# usb.net
KiCad netlist of a schematic drawn in Altium Designer
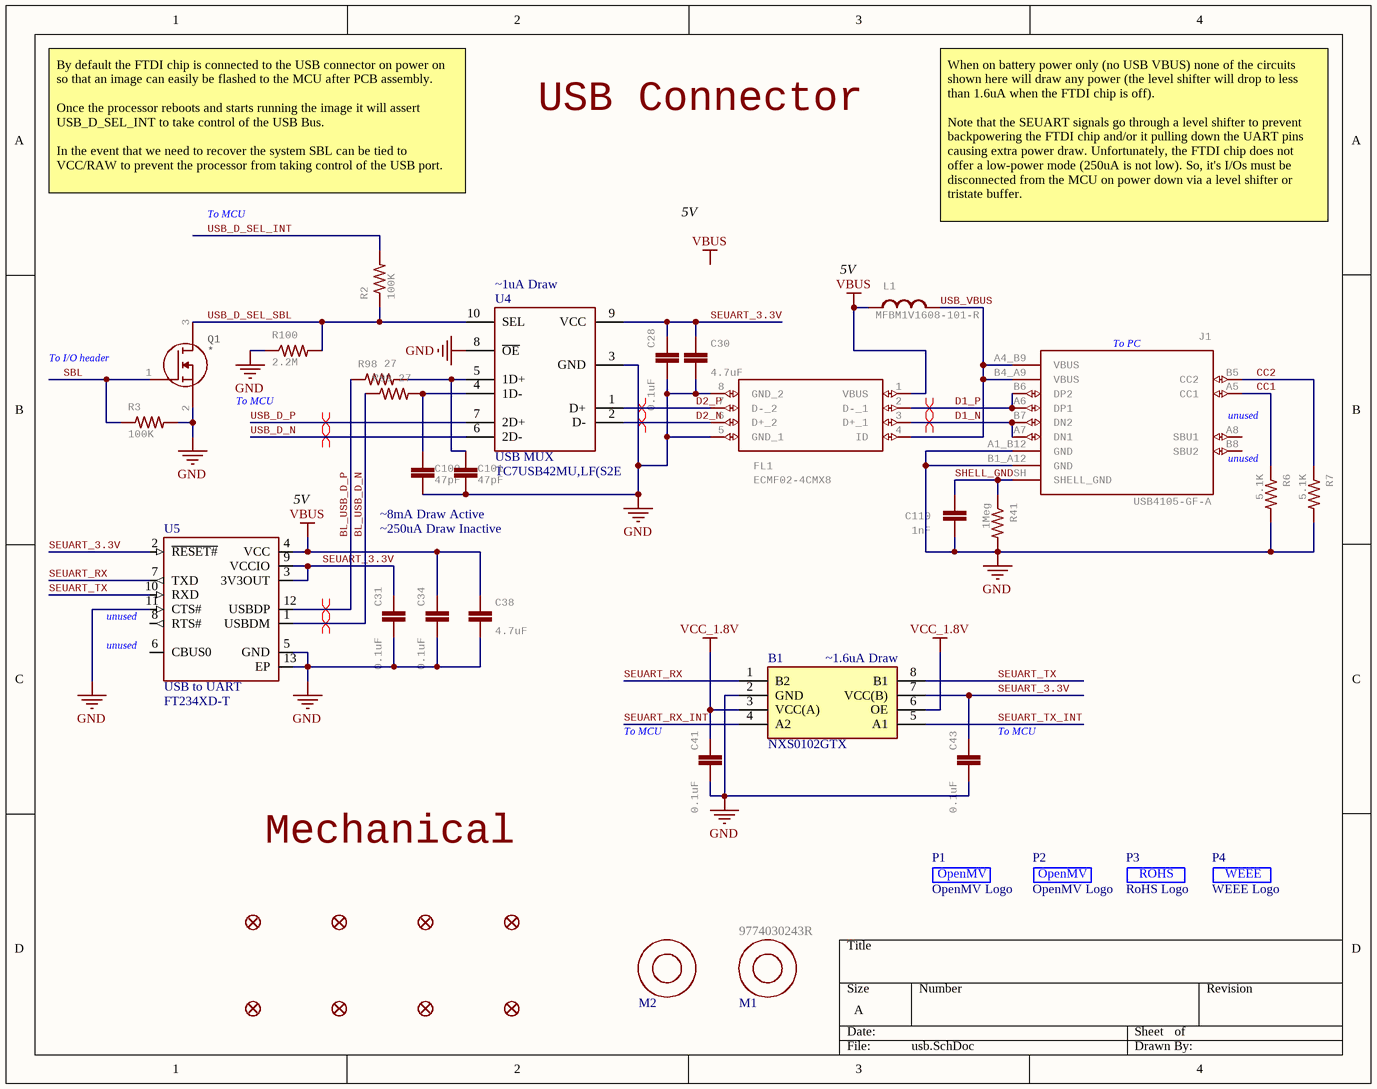
[diagram p0: usb.SchDoc]

(export (version "E")
  (design (tool "Eeschema 10.0.6"))
  (components
    (comp (ref "B1")
      (value "NXS0102GTX")
      (footprint "NXS0102GTX")
      (description "Dual supply translating transceiver; open drain; auto direction sensing")
      (fields (field (name "MOUSER PART NUMBER") "771-NXS0102GTX"))
      (libsource (lib "openmv-ae3") (part "NXS0102GTX"))
    )
    (comp (ref "C28")
      (value "0.1uF")
      (footprint "0402-CAP")
      (description "CAPACITOR, European symbol")
      (fields (field (name "MPN") "C0402C104Z4VAC"))
      (libsource (lib "openmv-ae3") (part "C-EUC0201"))
    )
    (comp (ref "C30")
      (value "4.7uF")
      (footprint "0402-CAP")
      (description "CapacitorStandard 0603 ceramic capacitor, and 0.1\" leaded capacitor.")
      (fields (field (name "MPN") "JMK105BBJ475MV-F") (field (name "LIBRARYNAME") "sfe"))
      (libsource (lib "") (part "CAP0402-CAP_1"))
    )
    (comp (ref "C31")
      (value "0.1uF")
      (footprint "0402-CAP")
      (description "CAPACITOR, European symbol")
      (fields (field (name "MPN") "C0402C104Z4VAC"))
      (libsource (lib "openmv-ae3") (part "C-EUC0201"))
    )
    (comp (ref "C34")
      (value "0.1uF")
      (footprint "0402-CAP")
      (description "CAPACITOR, European symbol")
      (fields (field (name "MPN") "C0402C104Z4VAC"))
      (libsource (lib "openmv-ae3") (part "C-EUC0201"))
    )
    (comp (ref "C38")
      (value "4.7uF")
      (footprint "0402-CAP")
      (description "CapacitorStandard 0603 ceramic capacitor, and 0.1\" leaded capacitor.")
      (fields (field (name "MPN") "JMK105BBJ475MV-F") (field (name "LIBRARYNAME") "sfe"))
      (libsource (lib "") (part "CAP0402-CAP_1"))
    )
    (comp (ref "C41")
      (value "0.1uF")
      (footprint "0402-CAP")
      (description "CAPACITOR, European symbol")
      (fields (field (name "MPN") "C0402C104Z4VAC"))
      (libsource (lib "openmv-ae3") (part "C-EUC0201"))
    )
    (comp (ref "C43")
      (value "0.1uF")
      (footprint "0402-CAP")
      (description "CAPACITOR, European symbol")
      (fields (field (name "MPN") "C0402C104Z4VAC"))
      (libsource (lib "openmv-ae3") (part "C-EUC0201"))
    )
    (comp (ref "C100")
      (value "47pF")
      (footprint "C0201")
      (description "CAPACITOR, European symbol")
      (libsource (lib "") (part "C-EUC0201_1"))
    )
    (comp (ref "C101")
      (value "47pF")
      (footprint "C0201")
      (description "CAPACITOR, European symbol")
      (libsource (lib "") (part "C-EUC0201_1"))
    )
    (comp (ref "C110")
      (value "1nF")
      (footprint "0402-CAP")
      (description "Capacitor")
      (fields (field (name "MPN") "VJ0402Y102JXACW1BC") (field (name "LIBRARYNAME") "sfe"))
      (libsource (lib "openmv-ae3") (part "CAP0402-CAP"))
    )
    (comp (ref "FD1")
      (value "FIDUCIAL1X2")
      (footprint "FIDUCIAL-1X2")
      (fields (field (name "LIBRARYNAME") "SparkFun-Aesthetics"))
      (libsource (lib "openmv-ae3") (part "FIDUCIAL1X2"))
    )
    (comp (ref "FD2")
      (value "FIDUCIAL1X2")
      (footprint "FIDUCIAL-1X2")
      (fields (field (name "LIBRARYNAME") "SparkFun-Aesthetics"))
      (libsource (lib "openmv-ae3") (part "FIDUCIAL1X2"))
    )
    (comp (ref "FD3")
      (value "FIDUCIAL1X2")
      (footprint "FIDUCIAL-1X2")
      (fields (field (name "LIBRARYNAME") "SparkFun-Aesthetics"))
      (libsource (lib "openmv-ae3") (part "FIDUCIAL1X2"))
    )
    (comp (ref "FD4")
      (value "FIDUCIAL1X2")
      (footprint "FIDUCIAL-1X2")
      (fields (field (name "LIBRARYNAME") "SparkFun-Aesthetics"))
      (libsource (lib "openmv-ae3") (part "FIDUCIAL1X2"))
    )
    (comp (ref "FD5")
      (value "FIDUCIAL1X2")
      (footprint "FIDUCIAL-1X2")
      (fields (field (name "LIBRARYNAME") "SparkFun-Aesthetics"))
      (libsource (lib "openmv-ae3") (part "FIDUCIAL1X2"))
    )
    (comp (ref "FD6")
      (value "FIDUCIAL1X2")
      (footprint "FIDUCIAL-1X2")
      (fields (field (name "LIBRARYNAME") "SparkFun-Aesthetics"))
      (libsource (lib "openmv-ae3") (part "FIDUCIAL1X2"))
    )
    (comp (ref "FD7")
      (value "FIDUCIAL1X2")
      (footprint "FIDUCIAL-1X2")
      (fields (field (name "LIBRARYNAME") "SparkFun-Aesthetics"))
      (libsource (lib "openmv-ae3") (part "FIDUCIAL1X2"))
    )
    (comp (ref "FD8")
      (value "FIDUCIAL1X2")
      (footprint "FIDUCIAL-1X2")
      (fields (field (name "LIBRARYNAME") "SparkFun-Aesthetics"))
      (libsource (lib "openmv-ae3") (part "FIDUCIAL1X2"))
    )
    (comp (ref "FL1")
      (value "ECMF02-4CMX8")
      (footprint "ECMF024CMX8")
      (fields (field (name "MOUSER_PART_NUMBER") "511-ECMF02-4CMX8"))
      (libsource (lib "openmv-ae3") (part "ECMF02-4CMX8"))
    )
    (comp (ref "J1")
      (value "USB4105-GF-A")
      (footprint "GCT_USB4105-GF-A")
      (fields (field (name "MF") "GCT"))
      (libsource (lib "openmv-ae3") (part "USB4105-GF-A"))
    )
    (comp (ref "L1")
      (value "MFBM1V1608-101-R")
      (footprint "0603-RES")
      (libsource (lib "openmv-ae3") (part "INDUCTOR"))
    )
    (comp (ref "M1")
      (value "9774030243R")
      (footprint "9774030243R")
      (description "M2 3mm Standoff")
      (libsource (lib "openmv-ae3") (part "9774030243R"))
    )
    (comp (ref "M2")
      (value "9774030243R")
      (footprint "9774030243R")
      (description "M2 3mm Standoff")
      (libsource (lib "openmv-ae3") (part "9774030243R"))
    )
    (comp (ref "P1")
      (value "OpenMV Logo")
      (footprint "OMV-LOGO-SMALL")
      (libsource (lib "openmv-ae3") (part "OMV"))
    )
    (comp (ref "P2")
      (value "OpenMV Logo")
      (footprint "OMV-LOGO-SMALL")
      (libsource (lib "openmv-ae3") (part "OMV"))
    )
    (comp (ref "P3") (value "RoHS Logo") (footprint "ROHS") (libsource (lib "openmv-ae3") (part "ROHS")))
    (comp (ref "P4") (value "WEEE Logo") (footprint "WEEE") (libsource (lib "openmv-ae3") (part "WEEE")))
    (comp (ref "Q1")
      (value "NMOS")
      (footprint "DFN1006")
      (fields (field (name "MPN") "*"))
      (libsource (lib "openmv-ae3") (part "NMOS"))
    )
    (comp (ref "R2")
      (value "100K")
      (footprint "R0201")
      (fields (field (name "LIBRARYNAME") "sfe"))
      (libsource (lib "openmv-ae3") (part "RESISTOR0402-RES"))
    )
    (comp (ref "R3")
      (value "100K")
      (footprint "R0201")
      (fields (field (name "LIBRARYNAME") "sfe"))
      (libsource (lib "openmv-ae3") (part "RESISTOR0402-RES"))
    )
    (comp (ref "R6")
      (value "5.1K")
      (footprint "0402-RES")
      (description "ResistorBasic schematic elements and footprints for 0603, 1206, and PTH resistors.")
      (fields (field (name "MPN") "RC0402JR-075K1L") (field (name "LIBRARYNAME") "sfe"))
      (libsource (lib "openmv-ae3") (part "RESISTOR0402-RES"))
    )
    (comp (ref "R7")
      (value "5.1K")
      (footprint "0402-RES")
      (description "ResistorBasic schematic elements and footprints for 0603, 1206, and PTH resistors.")
      (fields (field (name "MPN") "RC0402JR-075K1L") (field (name "LIBRARYNAME") "sfe"))
      (libsource (lib "openmv-ae3") (part "RESISTOR0402-RES"))
    )
    (comp (ref "R41")
      (value "1Meg")
      (footprint "0402-RES")
      (description "Resistor")
      (fields (field (name "MPN") "CRCW04021M00FKEDC") (field (name "LIBRARYNAME") "sfe"))
      (libsource (lib "openmv-ae3") (part "RESISTOR0402-RES"))
    )
    (comp (ref "R98")
      (value "27")
      (footprint "R0201")
      (fields (field (name "LIBRARYNAME") "sfe"))
      (libsource (lib "openmv-ae3") (part "RESISTOR0402-RES"))
    )
    (comp (ref "R99")
      (value "27")
      (footprint "R0201")
      (fields (field (name "LIBRARYNAME") "sfe"))
      (libsource (lib "openmv-ae3") (part "RESISTOR0402-RES"))
    )
    (comp (ref "R100")
      (value "2.2M")
      (footprint "R0201")
      (fields (field (name "LIBRARYNAME") "sfe"))
      (libsource (lib "openmv-ae3") (part "RESISTOR0402-RES"))
    )
    (comp (ref "U4")
      (value "USB MUX")
      (footprint "TC7USB42MU,LF(S2E")
      (fields (field (name "MF") "Toshiba") (field (name "MPN") "TC7USB42MU,LF(S2E"))
      (libsource (lib "openmv-ae3") (part "TC7USB42MU,LF(S2E"))
    )
    (comp (ref "U5")
      (value "USB to UART")
      (footprint "SON45P300X300X80-13N")
      (description "USB Bridge, USB to UART USB 2.0 UART Interface 12-DFN _3x3_")
      (fields
        (field (name "MF") "FTDI,")
        (field (name "PART NUMBER") "FT234XD-T")
        (field (name "MPN") "FT234XD-T")
      )
      (libsource (lib "openmv-ae3") (part "FT234XD-T"))
    )
  )
  (nets
    (net (code "1") (name "/BL_USB_D_N") (class "Default")
      (node (ref "R99") (pin "1") (pinfunction "1_1") (pintype "passive"))
      (node (ref "U5") (pin "1") (pinfunction "USBDM_1") (pintype "bidirectional"))
    )
    (net (code "2") (name "/BL_USB_D_P") (class "Default")
      (node (ref "R98") (pin "1") (pinfunction "1_1") (pintype "passive"))
      (node (ref "U5") (pin "12") (pinfunction "USBDP_12") (pintype "bidirectional"))
    )
    (net (code "3") (name "/CC1") (class "Default")
      (node (ref "J1") (pin "A5") (pinfunction "CC1_A5") (pintype "bidirectional"))
      (node (ref "R6") (pin "1") (pinfunction "1_1") (pintype "passive"))
    )
    (net (code "4") (name "/CC2") (class "Default")
      (node (ref "J1") (pin "B5") (pinfunction "CC2_B5") (pintype "bidirectional"))
      (node (ref "R7") (pin "1") (pinfunction "1_1") (pintype "passive"))
    )
    (net (code "5") (name "/D1_N") (class "Default")
      (node (ref "FL1") (pin "3") (pinfunction "D+_1_3") (pintype "bidirectional"))
      (node (ref "J1") (pin "A7") (pinfunction "DN1_A7") (pintype "bidirectional"))
      (node (ref "J1") (pin "B7") (pinfunction "DN2_B7") (pintype "bidirectional"))
    )
    (net (code "6") (name "/D1_P") (class "Default")
      (node (ref "FL1") (pin "2") (pinfunction "D-_1_2") (pintype "bidirectional"))
      (node (ref "J1") (pin "A6") (pinfunction "DP1_A6") (pintype "bidirectional"))
      (node (ref "J1") (pin "B6") (pinfunction "DP2_B6") (pintype "bidirectional"))
    )
    (net (code "7") (name "/D2_N") (class "Default")
      (node (ref "FL1") (pin "6") (pinfunction "D+_2_6") (pintype "bidirectional"))
      (node (ref "U4") (pin "2") (pinfunction "D-_2") (pintype "passive"))
    )
    (net (code "8") (name "/D2_P") (class "Default")
      (node (ref "FL1") (pin "7") (pinfunction "D-_2_7") (pintype "bidirectional"))
      (node (ref "U4") (pin "1") (pinfunction "D+_1") (pintype "passive"))
    )
    (net (code "9") (name "/SBL") (class "Default")
      (node (ref "Q1") (pin "1") (pinfunction "G_1") (pintype "bidirectional"))
      (node (ref "R3") (pin "1") (pinfunction "1_1") (pintype "passive"))
    )
    (net (code "10") (name "/SEUART_3.3V") (class "Default")
      (node (ref "B1") (pin "7") (pinfunction "VCC(B)_7") (pintype "passive"))
      (node (ref "C28") (pin "1") (pinfunction "1_1") (pintype "passive"))
      (node (ref "C30") (pin "2") (pinfunction "2_2") (pintype "passive"))
      (node (ref "C31") (pin "1") (pinfunction "1_1") (pintype "passive"))
      (node (ref "C43") (pin "1") (pinfunction "1_1") (pintype "passive"))
      (node (ref "U4") (pin "9") (pinfunction "VCC_9") (pintype "passive"))
      (node (ref "U5") (pin "2") (pinfunction "~{RESET#}_2") (pintype "input"))
      (node (ref "U5") (pin "3") (pinfunction "3V3OUT_3") (pintype "power_in"))
      (node (ref "U5") (pin "9") (pinfunction "VCCIO_9") (pintype "power_in"))
    )
    (net (code "11") (name "/SEUART_RX") (class "Default")
      (node (ref "B1") (pin "1") (pinfunction "B2_1") (pintype "passive"))
      (node (ref "U5") (pin "7") (pinfunction "TXD_7") (pintype "output"))
    )
    (net (code "12") (name "/SEUART_RX_INT") (class "Default")
      (node (ref "B1") (pin "4") (pinfunction "A2_4") (pintype "passive"))
    )
    (net (code "13") (name "/SEUART_TX") (class "Default")
      (node (ref "B1") (pin "8") (pinfunction "B1_8") (pintype "passive"))
      (node (ref "U5") (pin "10") (pinfunction "RXD_10") (pintype "input"))
    )
    (net (code "14") (name "/SEUART_TX_INT") (class "Default")
      (node (ref "B1") (pin "5") (pinfunction "A1_5") (pintype "passive"))
    )
    (net (code "15") (name "/SHELL_GND") (class "Default")
      (node (ref "C110") (pin "1") (pinfunction "1_1") (pintype "passive"))
      (node (ref "J1") (pin "SH") (pinfunction "SHELL_GND_SH") (pintype "power_in"))
      (node (ref "R41") (pin "1") (pinfunction "1_1") (pintype "passive"))
    )
    (net (code "16") (name "/USB_D_N") (class "Default")
      (node (ref "U4") (pin "6") (pinfunction "2D-_6") (pintype "passive"))
    )
    (net (code "17") (name "/USB_D_P") (class "Default")
      (node (ref "U4") (pin "7") (pinfunction "2D+_7") (pintype "passive"))
    )
    (net (code "18") (name "/USB_D_SEL_INT") (class "Default")
      (node (ref "R2") (pin "2") (pinfunction "2_2") (pintype "passive"))
    )
    (net (code "19") (name "/USB_D_SEL_SBL") (class "Default")
      (node (ref "Q1") (pin "3") (pinfunction "D_3") (pintype "bidirectional"))
      (node (ref "R100") (pin "2") (pinfunction "2_2") (pintype "passive"))
      (node (ref "R2") (pin "1") (pinfunction "1_1") (pintype "passive"))
      (node (ref "U4") (pin "10") (pinfunction "SEL_10") (pintype "passive"))
    )
    (net (code "20") (name "/USB_VBUS") (class "Default")
      (node (ref "FL1") (pin "4") (pinfunction "ID_4") (pintype "bidirectional"))
      (node (ref "J1") (pin "A4_B9") (pinfunction "VBUS_A4_B9") (pintype "power_in"))
      (node (ref "J1") (pin "B4_A9") (pinfunction "VBUS_B4_A9") (pintype "power_in"))
      (node (ref "L1") (pin "2") (pinfunction "2_2") (pintype "passive"))
    )
    (net (code "21") (name "GND") (class "Default")
      (node (ref "B1") (pin "2") (pinfunction "GND_2") (pintype "passive"))
      (node (ref "C100") (pin "1") (pinfunction "1_1") (pintype "passive"))
      (node (ref "C101") (pin "1") (pinfunction "1_1") (pintype "passive"))
      (node (ref "C110") (pin "2") (pinfunction "2_2") (pintype "passive"))
      (node (ref "C28") (pin "2") (pinfunction "2_2") (pintype "passive"))
      (node (ref "C30") (pin "1") (pinfunction "1_1") (pintype "passive"))
      (node (ref "C31") (pin "2") (pinfunction "2_2") (pintype "passive"))
      (node (ref "C34") (pin "2") (pinfunction "2_2") (pintype "passive"))
      (node (ref "C38") (pin "1") (pinfunction "1_1") (pintype "passive"))
      (node (ref "C41") (pin "2") (pinfunction "2_2") (pintype "passive"))
      (node (ref "C43") (pin "2") (pinfunction "2_2") (pintype "passive"))
      (node (ref "FL1") (pin "5") (pinfunction "GND_1_5") (pintype "bidirectional"))
      (node (ref "FL1") (pin "8") (pinfunction "GND_2_8") (pintype "bidirectional"))
      (node (ref "J1") (pin "A1_B12") (pinfunction "GND_A1_B12") (pintype "power_in"))
      (node (ref "J1") (pin "B1_A12") (pinfunction "GND_B1_A12") (pintype "power_in"))
      (node (ref "Q1") (pin "2") (pinfunction "S_2") (pintype "bidirectional"))
      (node (ref "R100") (pin "1") (pinfunction "1_1") (pintype "passive"))
      (node (ref "R3") (pin "2") (pinfunction "2_2") (pintype "passive"))
      (node (ref "R41") (pin "2") (pinfunction "2_2") (pintype "passive"))
      (node (ref "R6") (pin "2") (pinfunction "2_2") (pintype "passive"))
      (node (ref "R7") (pin "2") (pinfunction "2_2") (pintype "passive"))
      (node (ref "U4") (pin "3") (pinfunction "GND_3") (pintype "passive"))
      (node (ref "U4") (pin "8") (pinfunction "~{OE}_8") (pintype "passive"))
      (node (ref "U5") (pin "11") (pinfunction "CTS#_11") (pintype "input"))
      (node (ref "U5") (pin "13") (pinfunction "EP_13") (pintype "power_in"))
      (node (ref "U5") (pin "5") (pinfunction "GND_5") (pintype "power_in"))
    )
    (net (code "22") (name "Net-(U4-1D+)") (class "Default")
      (node (ref "C101") (pin "2") (pinfunction "2_2") (pintype "passive"))
      (node (ref "R98") (pin "2") (pinfunction "2_2") (pintype "passive"))
      (node (ref "U4") (pin "5") (pinfunction "1D+_5") (pintype "passive"))
    )
    (net (code "23") (name "Net-(U4-1D-)") (class "Default")
      (node (ref "C100") (pin "2") (pinfunction "2_2") (pintype "passive"))
      (node (ref "R99") (pin "2") (pinfunction "2_2") (pintype "passive"))
      (node (ref "U4") (pin "4") (pinfunction "1D-_4") (pintype "passive"))
    )
    (net (code "24") (name "VBUS") (class "Default")
      (node (ref "C34") (pin "1") (pinfunction "1_1") (pintype "passive"))
      (node (ref "C38") (pin "2") (pinfunction "2_2") (pintype "passive"))
      (node (ref "FL1") (pin "1") (pinfunction "VBUS_1") (pintype "bidirectional"))
      (node (ref "L1") (pin "1") (pinfunction "1_1") (pintype "passive"))
      (node (ref "U5") (pin "4") (pinfunction "VCC_4") (pintype "power_in"))
    )
    (net (code "25") (name "VCC_1.8V") (class "Default")
      (node (ref "B1") (pin "3") (pinfunction "VCC(A)_3") (pintype "passive"))
      (node (ref "B1") (pin "6") (pinfunction "OE_6") (pintype "passive"))
      (node (ref "C41") (pin "1") (pinfunction "1_1") (pintype "passive"))
    )
    (net (code "26") (name "unconnected-(J1-SBU1-PadA8)") (class "Default")
      (node (ref "J1") (pin "A8") (pinfunction "SBU1_A8") (pintype "bidirectional"))
    )
    (net (code "27") (name "unconnected-(J1-SBU2-PadB8)") (class "Default")
      (node (ref "J1") (pin "B8") (pinfunction "SBU2_B8") (pintype "bidirectional"))
    )
    (net (code "28") (name "unconnected-(U5-CBUS0-Pad6)") (class "Default")
      (node (ref "U5") (pin "6") (pinfunction "CBUS0_6") (pintype "bidirectional"))
    )
    (net (code "29") (name "unconnected-(U5-RTS#-Pad8)") (class "Default")
      (node (ref "U5") (pin "8") (pinfunction "RTS#_8") (pintype "output"))
    )
  )
)
